# sat-kim2.net
KiCad netlist of a schematic drawn in Altium Designer
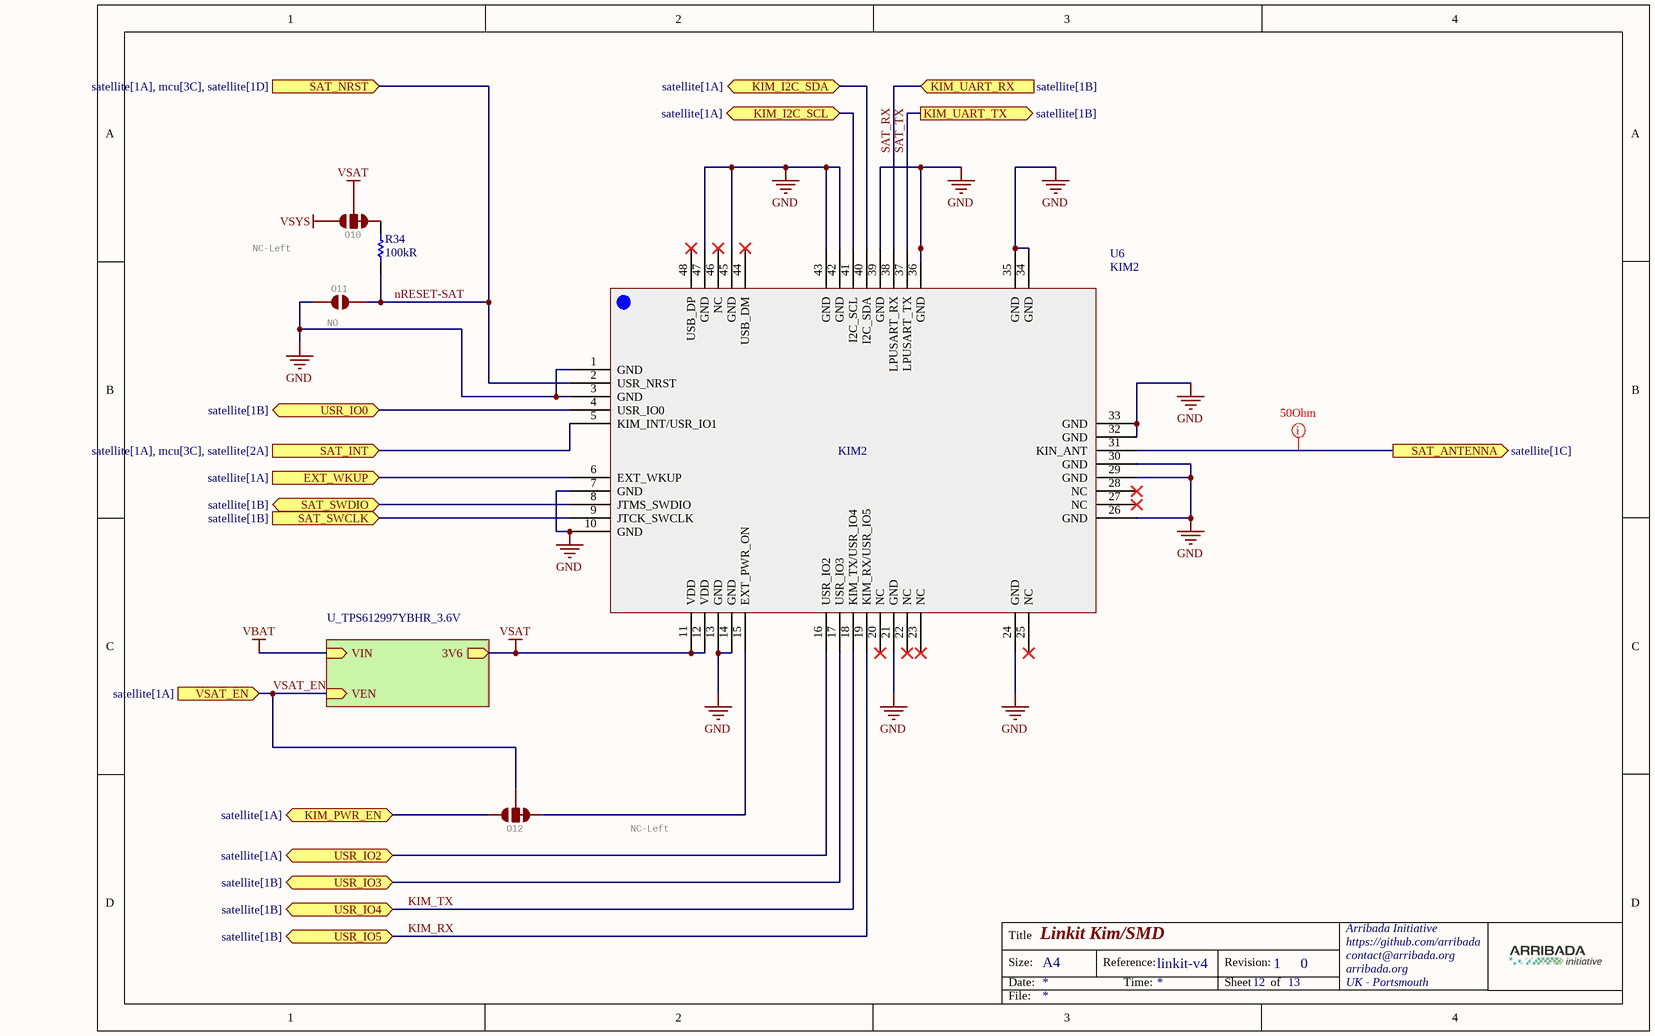
[diagram p0: sat-kim2.SchDoc]

(export (version "E")
  (design (tool "Eeschema 10.0.6"))
  (components
    (comp (ref "O10")
      (value "NC-Left")
      (footprint "SMT-JUMPER_3_2-NCLEFT_TRACE_SILK")
      (libsource (lib "stm32wl-dev") (part "JUMPER-SMT_3_2-NCLEFT_TRACE_SILK"))
    )
    (comp (ref "O11")
      (value "NO")
      (footprint "SMT-JUMPER_2_NO_TRACE_SILK")
      (libsource (lib "stm32wl-dev") (part "JUMPER-SMT_2_NO_TRACE_SILK_1"))
    )
    (comp (ref "O12")
      (value "NC-Left")
      (footprint "SMT-JUMPER_3_2-NCLEFT_TRACE_SILK")
      (libsource (lib "stm32wl-dev") (part "JUMPER-SMT_3_2-NCLEFT_TRACE_SILK"))
    )
    (comp (ref "R34")
      (value "100kR")
      (footprint "stm32wl-dev:RESC0603X28N")
      (description "Thick Film Resistors - SMD 1/20watt 100Kohms 5% 200ppm")
      (fields
        (field (name "MANUFACTURER_PART_NUMBER") "CRCW0201100KJNED")
        (field (name "MOUSER PART NUMBER") "71-CRCW0201100KJNED")
      )
      (libsource (lib "stm32wl-dev") (part "CRCW0201100KJNED"))
    )
    (comp (ref "U6")
      (value "KIM2")
      (footprint "KIM2 FOOTPRINT")
      (description "KIM2 Module 48 pins 1.27mm pitch 36.6 x 25.4 x 5mm")
      (fields (field (name "MANUFACTURER") "Kineis") (field (name "TOLERANCE") "-30 /  +55°C"))
      (libsource (lib "stm32wl-dev") (part "KIM2"))
    )
  )
  (nets
    (net (code "1") (name "/EXT_WKUP") (class "Default")
      (node (ref "U6") (pin "6") (pinfunction "EXT_WKUP_6") (pintype "passive"))
    )
    (net (code "2") (name "/KIM_I2C_SCL") (class "Default")
      (node (ref "U6") (pin "41") (pinfunction "I2C_SCL_41") (pintype "passive"))
    )
    (net (code "3") (name "/KIM_I2C_SDA") (class "Default")
      (node (ref "U6") (pin "40") (pinfunction "I2C_SDA_40") (pintype "passive"))
    )
    (net (code "4") (name "/KIM_PWR_EN") (class "Default")
      (node (ref "O12") (pin "3") (pinfunction "3_3") (pintype "passive"))
    )
    (net (code "5") (name "/KIM_RX") (class "Default")
      (node (ref "U6") (pin "19") (pinfunction "KIM_RX/USR_IO5_19") (pintype "passive"))
    )
    (net (code "6") (name "/KIM_TX") (class "Default")
      (node (ref "U6") (pin "18") (pinfunction "KIM_TX/USR_IO4_18") (pintype "passive"))
    )
    (net (code "7") (name "/SAT_ANTENNA") (class "Default")
      (node (ref "U6") (pin "31") (pinfunction "KIN_ANT_31") (pintype "passive"))
    )
    (net (code "8") (name "/SAT_INT") (class "Default")
      (node (ref "U6") (pin "5") (pinfunction "KIM_INT/USR_IO1_5") (pintype "passive"))
    )
    (net (code "9") (name "/SAT_RX") (class "Default")
      (node (ref "U6") (pin "38") (pinfunction "LPUSART_RX_38") (pintype "passive"))
    )
    (net (code "10") (name "/SAT_SWCLK") (class "Default")
      (node (ref "U6") (pin "9") (pinfunction "JTCK_SWCLK_9") (pintype "passive"))
    )
    (net (code "11") (name "/SAT_SWDIO") (class "Default")
      (node (ref "U6") (pin "8") (pinfunction "JTMS_SWDIO_8") (pintype "passive"))
    )
    (net (code "12") (name "/SAT_TX") (class "Default")
      (node (ref "U6") (pin "37") (pinfunction "LPUSART_TX_37") (pintype "passive"))
    )
    (net (code "13") (name "/USR_IO0") (class "Default")
      (node (ref "U6") (pin "4") (pinfunction "USR_IO0_4") (pintype "passive"))
    )
    (net (code "14") (name "/USR_IO2") (class "Default")
      (node (ref "U6") (pin "16") (pinfunction "USR_IO2_16") (pintype "passive"))
    )
    (net (code "15") (name "/USR_IO3") (class "Default")
      (node (ref "U6") (pin "17") (pinfunction "USR_IO3_17") (pintype "passive"))
    )
    (net (code "16") (name "/VSAT_EN") (class "Default")
      (node (ref "O12") (pin "2") (pinfunction "2_2") (pintype "passive"))
    )
    (net (code "17") (name "/nRESET-SAT") (class "Default")
      (node (ref "O11") (pin "2") (pinfunction "2_2") (pintype "passive"))
      (node (ref "R34") (pin "1") (pinfunction "1_1") (pintype "passive"))
      (node (ref "U6") (pin "2") (pinfunction "USR_NRST_2") (pintype "passive"))
    )
    (net (code "18") (name "GND") (class "Default")
      (node (ref "O11") (pin "1") (pinfunction "1_1") (pintype "passive"))
      (node (ref "U6") (pin "1") (pinfunction "GND_1") (pintype "passive"))
      (node (ref "U6") (pin "10") (pinfunction "GND_10") (pintype "passive"))
      (node (ref "U6") (pin "13") (pinfunction "GND_13") (pintype "passive"))
      (node (ref "U6") (pin "14") (pinfunction "GND_14") (pintype "passive"))
      (node (ref "U6") (pin "21") (pinfunction "GND_21") (pintype "passive"))
      (node (ref "U6") (pin "24") (pinfunction "GND_24") (pintype "passive"))
      (node (ref "U6") (pin "26") (pinfunction "GND_26") (pintype "passive"))
      (node (ref "U6") (pin "29") (pinfunction "GND_29") (pintype "passive"))
      (node (ref "U6") (pin "3") (pinfunction "GND_3") (pintype "passive"))
      (node (ref "U6") (pin "30") (pinfunction "GND_30") (pintype "passive"))
      (node (ref "U6") (pin "32") (pinfunction "GND_32") (pintype "passive"))
      (node (ref "U6") (pin "33") (pinfunction "GND_33") (pintype "passive"))
      (node (ref "U6") (pin "34") (pinfunction "GND_34") (pintype "passive"))
      (node (ref "U6") (pin "35") (pinfunction "GND_35") (pintype "passive"))
      (node (ref "U6") (pin "36") (pinfunction "GND_36") (pintype "passive"))
      (node (ref "U6") (pin "39") (pinfunction "GND_39") (pintype "passive"))
      (node (ref "U6") (pin "42") (pinfunction "GND_42") (pintype "passive"))
      (node (ref "U6") (pin "43") (pinfunction "GND_43") (pintype "passive"))
      (node (ref "U6") (pin "45") (pinfunction "GND_45") (pintype "passive"))
      (node (ref "U6") (pin "47") (pinfunction "GND_47") (pintype "passive"))
      (node (ref "U6") (pin "7") (pinfunction "GND_7") (pintype "passive"))
    )
    (net (code "19") (name "Net-(O10-Pad1)") (class "Default")
      (node (ref "O10") (pin "1") (pinfunction "1_1") (pintype "passive"))
      (node (ref "R34") (pin "2") (pinfunction "2_2") (pintype "passive"))
    )
    (net (code "20") (name "Net-(U6-EXT_PWR_ON)") (class "Default")
      (node (ref "O12") (pin "1") (pinfunction "1_1") (pintype "passive"))
      (node (ref "U6") (pin "15") (pinfunction "EXT_PWR_ON_15") (pintype "passive"))
    )
    (net (code "22") (name "VSAT") (class "Default")
      (node (ref "O10") (pin "2") (pinfunction "2_2") (pintype "passive"))
      (node (ref "U6") (pin "11") (pinfunction "VDD_11") (pintype "passive"))
      (node (ref "U6") (pin "12") (pinfunction "VDD_12") (pintype "passive"))
    )
    (net (code "23") (name "VSYS") (class "Default")
      (node (ref "O10") (pin "3") (pinfunction "3_3") (pintype "passive"))
    )
    (net (code "24") (name "unconnected-(U6-NC-Pad20)") (class "Default")
      (node (ref "U6") (pin "20") (pinfunction "NC_20") (pintype "passive+no_connect"))
    )
    (net (code "25") (name "unconnected-(U6-NC-Pad22)") (class "Default")
      (node (ref "U6") (pin "22") (pinfunction "NC_22") (pintype "passive+no_connect"))
    )
    (net (code "26") (name "unconnected-(U6-NC-Pad23)") (class "Default")
      (node (ref "U6") (pin "23") (pinfunction "NC_23") (pintype "passive+no_connect"))
    )
    (net (code "27") (name "unconnected-(U6-NC-Pad25)") (class "Default")
      (node (ref "U6") (pin "25") (pinfunction "NC_25") (pintype "passive+no_connect"))
    )
    (net (code "28") (name "unconnected-(U6-NC-Pad27)") (class "Default")
      (node (ref "U6") (pin "27") (pinfunction "NC_27") (pintype "passive+no_connect"))
    )
    (net (code "29") (name "unconnected-(U6-NC-Pad28)") (class "Default")
      (node (ref "U6") (pin "28") (pinfunction "NC_28") (pintype "passive+no_connect"))
    )
    (net (code "30") (name "unconnected-(U6-NC-Pad46)") (class "Default")
      (node (ref "U6") (pin "46") (pinfunction "NC_46") (pintype "passive+no_connect"))
    )
    (net (code "31") (name "unconnected-(U6-USB_DM-Pad44)") (class "Default")
      (node (ref "U6") (pin "44") (pinfunction "USB_DM_44") (pintype "passive+no_connect"))
    )
    (net (code "32") (name "unconnected-(U6-USB_DP-Pad48)") (class "Default")
      (node (ref "U6") (pin "48") (pinfunction "USB_DP_48") (pintype "passive+no_connect"))
    )
  )
)
